# Bluetooth.net
KiCad netlist of a schematic drawn in Altium Designer
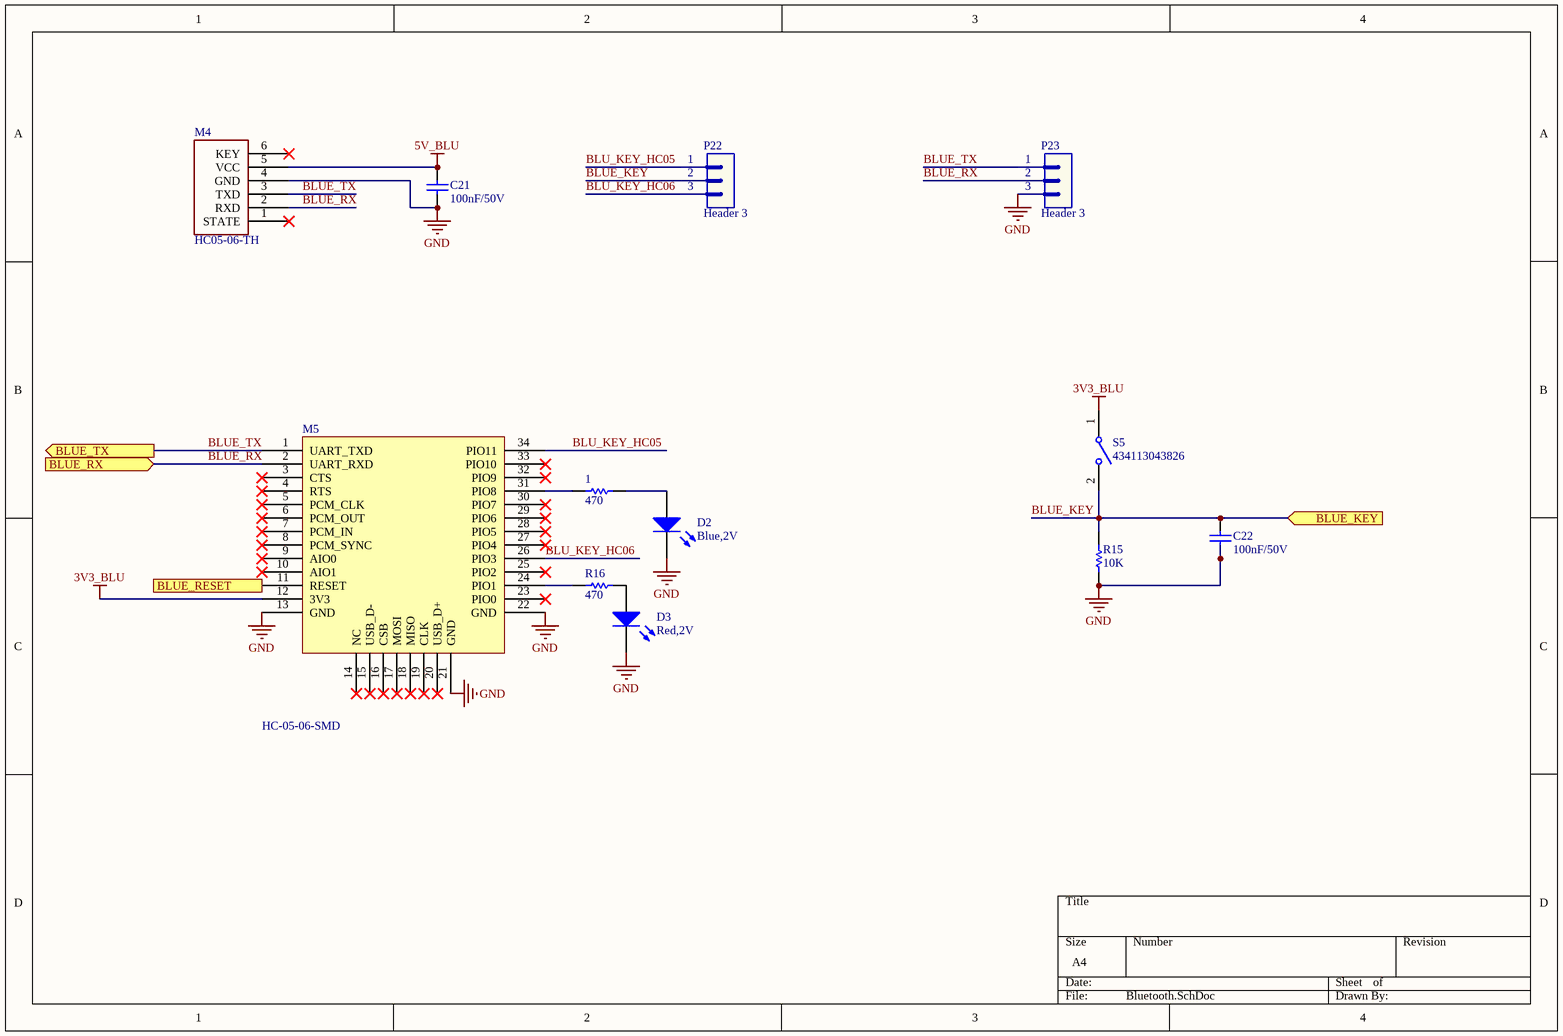
[diagram p0: Bluetooth.SchDoc]

(export (version "E")
  (design (tool "Eeschema 10.0.6"))
  (components
    (comp (ref "1")
      (value "470")
      (footprint "Resistor:RES-SM-0805")
      (description "RES 1K OHM 1% 1/4W 0805")
      (fields
        (field (name "MANUFACTURER") "Stackpole Electronics Inc")
        (field (name "MANUFACTURER PART NUMBER") "RNCP0805FTD1K00")
      )
      (libsource (lib "Resistor") (part "Res-1K-0805"))
    )
    (comp (ref "C21")
      (value "100nF/50V")
      (footprint "CAP-SM-0805")
      (description "CAP CER 1000PF 100V X7R 0805")
      (fields
        (field (name "MANUFACTURER") "Johanson Dielectrics Inc.")
        (field (name "MANUFACTURER PART NUMBER") "101X15W102MV4E")
      )
      (libsource (lib "Capacitor") (part "Cap-1nF-50V-0805"))
    )
    (comp (ref "C22")
      (value "100nF/50V")
      (footprint "CAP-SM-0805")
      (description "CAP CER 1000PF 100V X7R 0805")
      (fields
        (field (name "MANUFACTURER") "Johanson Dielectrics Inc.")
        (field (name "MANUFACTURER PART NUMBER") "101X15W102MV4E")
      )
      (libsource (lib "Capacitor") (part "Cap-1nF-50V-0805"))
    )
    (comp (ref "D2")
      (value "Blue,2V")
      (footprint "LED-3mm")
      (description "LED BLUE CLEAR T-1 T/H")
      (fields
        (field (name "MANUFACTURER") "Kingbright")
        (field (name "MANUFACTURER PART NUMBER") "WP710A10QBC/D")
      )
      (libsource (lib "LED") (part "LED-BLUE-TH-3mm"))
    )
    (comp (ref "D3")
      (value "Red,2V")
      (footprint "LED-3mm")
      (description "LED RED CLEAR T-1 T/H")
      (fields
        (field (name "MANUFACTURER") "Kingbright")
        (field (name "MANUFACTURER PART NUMBER") "WP710A10SEC/J3")
      )
      (libsource (lib "LED") (part "LED-RED-TH-3mm"))
    )
    (comp (ref "M4")
      (value "HC05-06-TH")
      (footprint "HC-05-06-TH")
      (libsource (lib "Schlib1") (part "HC05-06-TH"))
    )
    (comp (ref "M5")
      (value "HC-05-06-SMD")
      (footprint "HC-05-06-SMD")
      (libsource (lib "Integrated_Library_Test") (part "HC-05-06-SMD"))
    )
    (comp (ref "P22")
      (value "Header 3")
      (footprint "JP3")
      (description "Header, 3-Pin")
      (fields (field (name "PUBLISHER") "Altium Limited"))
      (libsource (lib "PIF_C16_lib") (part "Header 3"))
    )
    (comp (ref "P23")
      (value "Header 3")
      (footprint "JP3")
      (description "Header, 3-Pin")
      (fields (field (name "PUBLISHER") "Altium Limited"))
      (libsource (lib "PIF_C16_lib") (part "Header 3"))
    )
    (comp (ref "R15")
      (value "10K")
      (footprint "Resistor:RES-SM-0805")
      (description "RES 0 OHM JUMPER 0805")
      (fields
        (field (name "MANUFACTURER") "Vishay Dale")
        (field (name "MANUFACTURER PART NUMBER") "WSL080500000ZEA9")
      )
      (libsource (lib "Resistor") (part "Res-0-0805"))
    )
    (comp (ref "R16")
      (value "470")
      (footprint "Resistor:RES-SM-0805")
      (description "RES 1K OHM 1% 1/4W 0805")
      (fields
        (field (name "MANUFACTURER") "Stackpole Electronics Inc")
        (field (name "MANUFACTURER PART NUMBER") "RNCP0805FTD1K00")
      )
      (libsource (lib "Resistor") (part "Res-1K-0805"))
    )
    (comp (ref "S5")
      (value "434113043826")
      (footprint "434113043826")
      (description "WS-TASV J-Bend SMT Tact Switch 6x3.5mm, height 4.3mm, 260gf")
      (fields (field (name "PUBLISHER") "Wurth Elektronik"))
      (libsource (lib "434113043826_Altium_WS-TASV_rev20a") (part "434113043826"))
    )
  )
  (nets
    (net (code "1") (name "/BLUE_KEY") (class "Default")
      (node (ref "C22") (pin "2") (pinfunction "2_2") (pintype "passive"))
      (node (ref "P22") (pin "2") (pinfunction "2_2") (pintype "passive"))
      (node (ref "R15") (pin "1") (pinfunction "1_1") (pintype "passive"))
      (node (ref "S5") (pin "2") (pinfunction "2_2") (pintype "passive"))
    )
    (net (code "2") (name "/BLUE_RESET") (class "Default")
      (node (ref "M5") (pin "11") (pinfunction "RESET_11") (pintype "passive"))
    )
    (net (code "3") (name "/BLUE_RX") (class "Default")
      (node (ref "M4") (pin "2") (pinfunction "RXD_2") (pintype "passive"))
      (node (ref "M5") (pin "2") (pinfunction "UART_RXD_2") (pintype "passive"))
      (node (ref "P23") (pin "2") (pinfunction "2_2") (pintype "passive"))
    )
    (net (code "4") (name "/BLUE_TX") (class "Default")
      (node (ref "M4") (pin "3") (pinfunction "TXD_3") (pintype "passive"))
      (node (ref "M5") (pin "1") (pinfunction "UART_TXD_1") (pintype "passive"))
      (node (ref "P23") (pin "1") (pinfunction "1_1") (pintype "passive"))
    )
    (net (code "5") (name "/BLU_KEY_HC05") (class "Default")
      (node (ref "M5") (pin "34") (pinfunction "PIO11_34") (pintype "passive"))
      (node (ref "P22") (pin "1") (pinfunction "1_1") (pintype "passive"))
    )
    (net (code "6") (name "/BLU_KEY_HC06") (class "Default")
      (node (ref "M5") (pin "26") (pinfunction "PIO3_26") (pintype "passive"))
      (node (ref "P22") (pin "3") (pinfunction "3_3") (pintype "passive"))
    )
    (net (code "7") (name "3V3_BLU") (class "Default")
      (node (ref "M5") (pin "12") (pinfunction "3V3_12") (pintype "passive"))
      (node (ref "S5") (pin "1") (pinfunction "1_1") (pintype "passive"))
    )
    (net (code "8") (name "5V_BLU") (class "Default")
      (node (ref "C21") (pin "2") (pinfunction "2_2") (pintype "passive"))
      (node (ref "M4") (pin "5") (pinfunction "VCC_5") (pintype "passive"))
    )
    (net (code "9") (name "GND") (class "Default")
      (node (ref "C21") (pin "1") (pinfunction "1_1") (pintype "passive"))
      (node (ref "C22") (pin "1") (pinfunction "1_1") (pintype "passive"))
      (node (ref "D2") (pin "2") (pinfunction "K_2") (pintype "passive"))
      (node (ref "D3") (pin "2") (pinfunction "K_2") (pintype "passive"))
      (node (ref "M4") (pin "4") (pinfunction "GND_4") (pintype "passive"))
      (node (ref "M5") (pin "13") (pinfunction "GND_13") (pintype "passive"))
      (node (ref "M5") (pin "21") (pinfunction "GND_21") (pintype "passive"))
      (node (ref "M5") (pin "22") (pinfunction "GND_22") (pintype "passive"))
      (node (ref "P23") (pin "3") (pinfunction "3_3") (pintype "passive"))
      (node (ref "R15") (pin "2") (pinfunction "2_2") (pintype "passive"))
    )
    (net (code "10") (name "Net-(D2-A)") (class "Default")
      (node (ref "1") (pin "2") (pinfunction "2_2") (pintype "passive"))
      (node (ref "D2") (pin "1") (pinfunction "A_1") (pintype "passive"))
    )
    (net (code "11") (name "Net-(D3-A)") (class "Default")
      (node (ref "D3") (pin "1") (pinfunction "A_1") (pintype "passive"))
      (node (ref "R16") (pin "2") (pinfunction "2_2") (pintype "passive"))
    )
    (net (code "12") (name "Net-(M5-PIO1)") (class "Default")
      (node (ref "M5") (pin "24") (pinfunction "PIO1_24") (pintype "passive"))
      (node (ref "R16") (pin "1") (pinfunction "1_1") (pintype "passive"))
    )
    (net (code "13") (name "Net-(M5-PIO8)") (class "Default")
      (node (ref "1") (pin "1") (pinfunction "1_1") (pintype "passive"))
      (node (ref "M5") (pin "31") (pinfunction "PIO8_31") (pintype "passive"))
    )
    (net (code "14") (name "unconnected-(M4-KEY-Pad6)") (class "Default")
      (node (ref "M4") (pin "6") (pinfunction "KEY_6") (pintype "passive+no_connect"))
    )
    (net (code "15") (name "unconnected-(M4-STATE-Pad1)") (class "Default")
      (node (ref "M4") (pin "1") (pinfunction "STATE_1") (pintype "passive+no_connect"))
    )
    (net (code "16") (name "unconnected-(M5-AIO0-Pad9)") (class "Default")
      (node (ref "M5") (pin "9") (pinfunction "AIO0_9") (pintype "passive+no_connect"))
    )
    (net (code "17") (name "unconnected-(M5-AIO1-Pad10)") (class "Default")
      (node (ref "M5") (pin "10") (pinfunction "AIO1_10") (pintype "passive+no_connect"))
    )
    (net (code "18") (name "unconnected-(M5-CLK-Pad19)") (class "Default")
      (node (ref "M5") (pin "19") (pinfunction "CLK_19") (pintype "passive+no_connect"))
    )
    (net (code "19") (name "unconnected-(M5-CSB-Pad16)") (class "Default")
      (node (ref "M5") (pin "16") (pinfunction "CSB_16") (pintype "passive+no_connect"))
    )
    (net (code "20") (name "unconnected-(M5-CTS-Pad3)") (class "Default")
      (node (ref "M5") (pin "3") (pinfunction "CTS_3") (pintype "passive+no_connect"))
    )
    (net (code "21") (name "unconnected-(M5-MISO-Pad18)") (class "Default")
      (node (ref "M5") (pin "18") (pinfunction "MISO_18") (pintype "passive+no_connect"))
    )
    (net (code "22") (name "unconnected-(M5-MOSI-Pad17)") (class "Default")
      (node (ref "M5") (pin "17") (pinfunction "MOSI_17") (pintype "passive+no_connect"))
    )
    (net (code "23") (name "unconnected-(M5-NC-Pad14)") (class "Default")
      (node (ref "M5") (pin "14") (pinfunction "NC_14") (pintype "passive+no_connect"))
    )
    (net (code "24") (name "unconnected-(M5-PCM_CLK-Pad5)") (class "Default")
      (node (ref "M5") (pin "5") (pinfunction "PCM_CLK_5") (pintype "passive+no_connect"))
    )
    (net (code "25") (name "unconnected-(M5-PCM_IN-Pad7)") (class "Default")
      (node (ref "M5") (pin "7") (pinfunction "PCM_IN_7") (pintype "passive+no_connect"))
    )
    (net (code "26") (name "unconnected-(M5-PCM_OUT-Pad6)") (class "Default")
      (node (ref "M5") (pin "6") (pinfunction "PCM_OUT_6") (pintype "passive+no_connect"))
    )
    (net (code "27") (name "unconnected-(M5-PCM_SYNC-Pad8)") (class "Default")
      (node (ref "M5") (pin "8") (pinfunction "PCM_SYNC_8") (pintype "passive+no_connect"))
    )
    (net (code "28") (name "unconnected-(M5-PIO0-Pad23)") (class "Default")
      (node (ref "M5") (pin "23") (pinfunction "PIO0_23") (pintype "passive+no_connect"))
    )
    (net (code "29") (name "unconnected-(M5-PIO2-Pad25)") (class "Default")
      (node (ref "M5") (pin "25") (pinfunction "PIO2_25") (pintype "passive+no_connect"))
    )
    (net (code "30") (name "unconnected-(M5-PIO4-Pad27)") (class "Default")
      (node (ref "M5") (pin "27") (pinfunction "PIO4_27") (pintype "passive+no_connect"))
    )
    (net (code "31") (name "unconnected-(M5-PIO5-Pad28)") (class "Default")
      (node (ref "M5") (pin "28") (pinfunction "PIO5_28") (pintype "passive+no_connect"))
    )
    (net (code "32") (name "unconnected-(M5-PIO6-Pad29)") (class "Default")
      (node (ref "M5") (pin "29") (pinfunction "PIO6_29") (pintype "passive+no_connect"))
    )
    (net (code "33") (name "unconnected-(M5-PIO7-Pad30)") (class "Default")
      (node (ref "M5") (pin "30") (pinfunction "PIO7_30") (pintype "passive+no_connect"))
    )
    (net (code "34") (name "unconnected-(M5-PIO9-Pad32)") (class "Default")
      (node (ref "M5") (pin "32") (pinfunction "PIO9_32") (pintype "passive+no_connect"))
    )
    (net (code "35") (name "unconnected-(M5-PIO10-Pad33)") (class "Default")
      (node (ref "M5") (pin "33") (pinfunction "PIO10_33") (pintype "passive+no_connect"))
    )
    (net (code "36") (name "unconnected-(M5-RTS-Pad4)") (class "Default")
      (node (ref "M5") (pin "4") (pinfunction "RTS_4") (pintype "passive+no_connect"))
    )
    (net (code "37") (name "unconnected-(M5-USB_D+-Pad20)") (class "Default")
      (node (ref "M5") (pin "20") (pinfunction "USB_D+_20") (pintype "passive+no_connect"))
    )
    (net (code "38") (name "unconnected-(M5-USB_D--Pad15)") (class "Default")
      (node (ref "M5") (pin "15") (pinfunction "USB_D-_15") (pintype "passive+no_connect"))
    )
  )
)
